# 00_POWER.net
KiCad netlist of a schematic drawn in Altium Designer
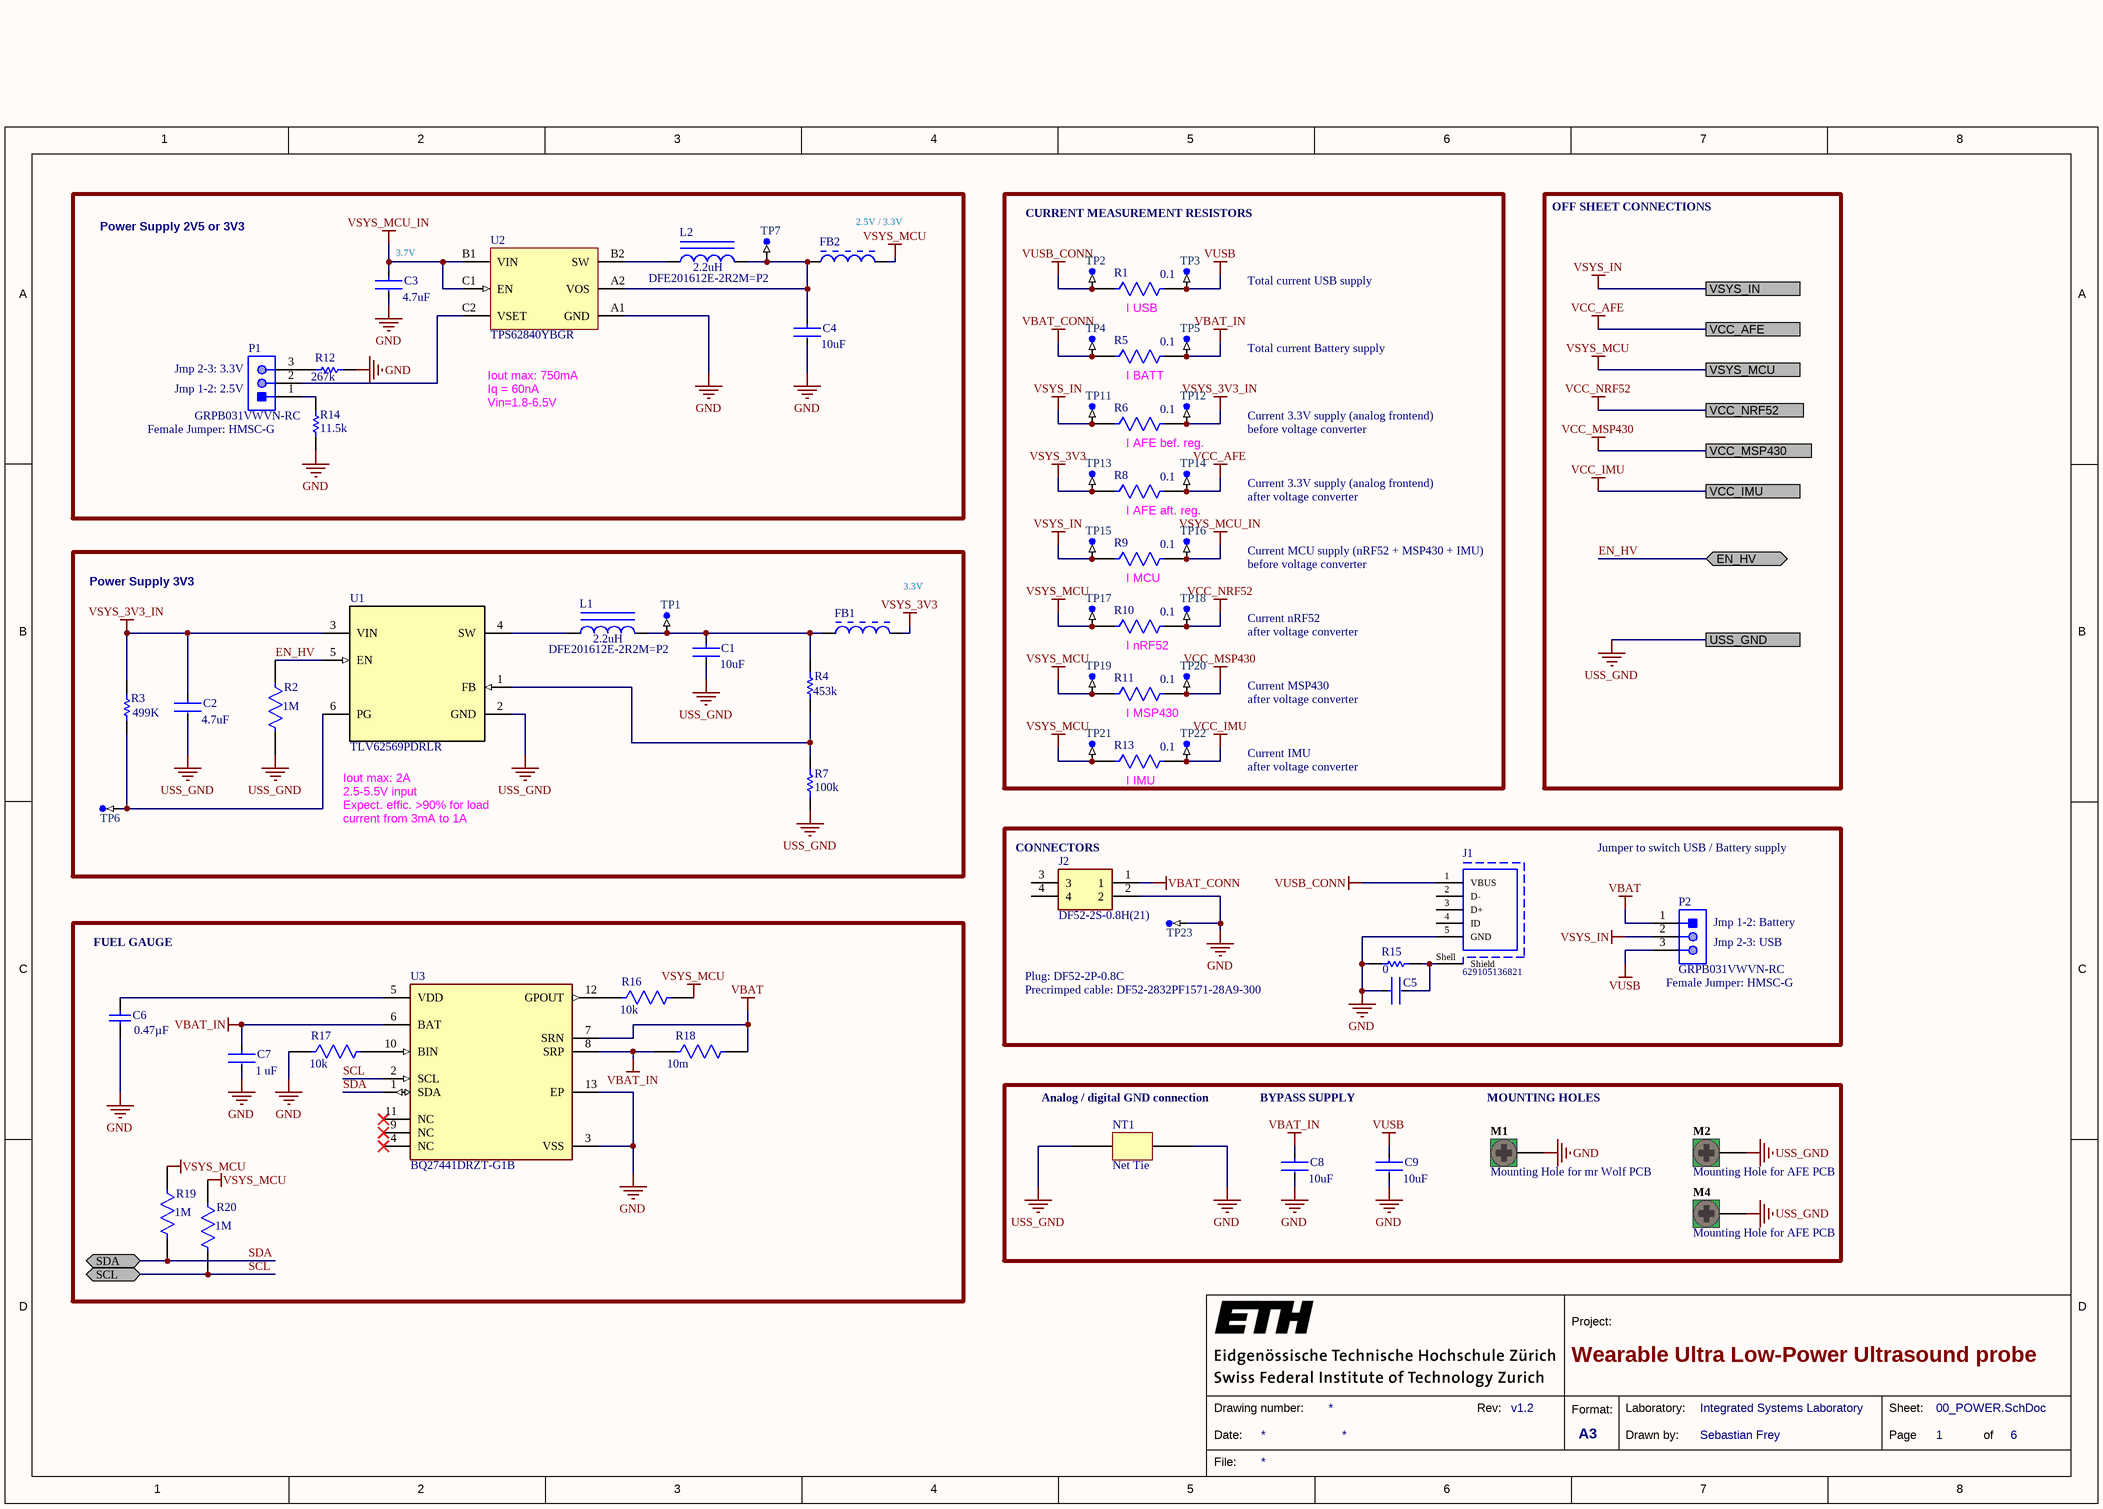
[diagram p0: 00_POWER.SchDoc]

(export (version "E")
  (design (tool "Eeschema 10.0.6"))
  (components
    (comp (ref "C1")
      (value "10uF")
      (footprint "FP-C1608-080-MFG")
      (description "CAP CER 10UF 10V X5R 0603")
      (fields
        (field (name "MANUFACTURER PART NUMBER") "C1608X5R1A106K080AC")
        (field (name "OCTOPART") "https://octopart.com/c1608x5r1a106k080ac-tdk-26013468")
      )
      (libsource (lib "Altium Content Vault") (part "11868f565c42a9108669ba33697ecf6"))
    )
    (comp (ref "C2")
      (value "EMK107ABJ475KA-T")
      (footprint "FP-0603-L_1_6_0_15-W_0_8-IPC_A")
      (description "None")
      (fields (field (name "CAPACITANCE") "4.7uF") (field (name "TOLERANCE") "10%"))
      (libsource (lib "Altium Content Vault") (part "11868f565c42a9108669ba33697ecf6"))
    )
    (comp (ref "C3")
      (value "EMK107ABJ475KA-T")
      (footprint "FP-0603-L_1_6_0_15-W_0_8-IPC_A")
      (description "None")
      (fields (field (name "CAPACITANCE") "4.7uF") (field (name "TOLERANCE") "10%"))
      (libsource (lib "Altium Content Vault") (part "11868f565c42a9108669ba33697ecf6"))
    )
    (comp (ref "C4")
      (value "10uF")
      (footprint "FP-C1608-080-MFG")
      (description "CAP CER 10UF 10V X5R 0603")
      (fields
        (field (name "MANUFACTURER PART NUMBER") "C1608X5R1A106K080AC")
        (field (name "OCTOPART") "https://octopart.com/c1608x5r1a106k080ac-tdk-26013468")
      )
      (libsource (lib "Altium Content Vault") (part "11868f565c42a9108669ba33697ecf6"))
    )
    (comp (ref "C5")
      (value "CC0402KRX7R7BB104")
      (footprint "FP-CC0402-MFG")
      (description "CAP CER 0.1UF 16V X7R 0402")
      (fields (field (name "MANUFACTURER") "YAGEO") (field (name "TOLERANCE") "0.1"))
      (libsource (lib "Altium Content Vault") (part "11868f565c42a9108669ba33697ecf6"))
    )
    (comp (ref "C6")
      (value "C1005X5R1E474K050BB")
      (footprint "CAPC1050X55X10LL05")
      (description "Chip Capacitor, 0.47 uF, +/- 10%, 25 V, -55 to 85 degC, 0402 (1005 Metric), RoHS, Tape and Reel")
      (fields
        (field (name "CAPACITANCE") "0.47µF")
        (field (name "TOLERANCE") "±10%")
        (field (name "PCN PART NUMBER") "MLCCPartNumberChange30/Nov/2012")
      )
      (libsource (lib "Altium Content Vault") (part "CAP-NP-2"))
    )
    (comp (ref "C7")
      (value "CC0402KRX5R5BB105")
      (footprint "FP-CC0402-MFG")
      (description "CAP CER 1UF 6.3V X5R 0402")
      (fields
        (field (name "CAPACITANCE") "1 uF")
        (field (name "MANUFACTURER") "YAGEO")
        (field (name "OCTOPART") "https://octopart.com/cc0402krx5r5bb105-yageo-42244618")
      )
      (libsource (lib "Altium Content Vault") (part "11868f565c42a9108669ba33697ecf6"))
    )
    (comp (ref "C8")
      (value "10uF")
      (footprint "FP-C1608-080-MFG")
      (description "CAP CER 10UF 10V X5R 0603")
      (fields
        (field (name "MANUFACTURER PART NUMBER") "C1608X5R1A106K080AC")
        (field (name "OCTOPART") "https://octopart.com/c1608x5r1a106k080ac-tdk-26013468")
      )
      (libsource (lib "Altium Content Vault") (part "11868f565c42a9108669ba33697ecf6"))
    )
    (comp (ref "C9")
      (value "10uF")
      (footprint "FP-C1608-080-MFG")
      (description "CAP CER 10UF 10V X5R 0603")
      (fields
        (field (name "MANUFACTURER PART NUMBER") "C1608X5R1A106K080AC")
        (field (name "OCTOPART") "https://octopart.com/c1608x5r1a106k080ac-tdk-26013468")
      )
      (libsource (lib "Altium Content Vault") (part "11868f565c42a9108669ba33697ecf6"))
    )
    (comp (ref "FB1")
      (value "BLM03AX800SN1D")
      (footprint "MURA-BLM03-CHIP-2_V")
      (fields (field (name "MANUFACTURER") "Murata") (field (name "TOLERANCE") "25%"))
      (libsource (lib "Altium Content Vault") (part "MURA-FB-2"))
    )
    (comp (ref "FB2")
      (value "BLM03AX800SN1D")
      (footprint "MURA-BLM03-CHIP-2_V")
      (fields (field (name "MANUFACTURER") "Murata") (field (name "TOLERANCE") "25%"))
      (libsource (lib "Altium Content Vault") (part "MURA-FB-2"))
    )
    (comp (ref "J1")
      (value "629105136821")
      (footprint "629105136821")
      (description "Micro USB 2.0 Type B Receptacle WR-COM, Horizontal, SMT, with Pads and Pegs")
      (fields (field (name "MANUFACTURER") "Wurth Elektronik") (field (name "PUBLISHER") "WurthElektronik"))
      (libsource (lib "Altium Content Vault") (part "WE-USB-5-1SHLD"))
    )
    (comp (ref "J2")
      (value "DF52-2S-0.8H(21)")
      (footprint "SamacSys:DF522S08H21")
      (description "Connector")
      (fields (field (name "MOUSER PART NUMBER") "798-DF52-2S-0.8H21"))
      (libsource (lib "*") (part "DF52-2S-0.8H_21_"))
    )
    (comp (ref "L1")
      (value "DFE201612E-2R2M=P2")
      (footprint "INDC2016X10L")
      (description "2.2µH Shielded Wirewound Inductor 1.8A 116mOhm Max 0806 (2016 Metric)")
      (fields
        (field (name "ALTIUM_VALUE") "2.2uH")
        (field (name "TOLERANCE") "±20%")
        (field (name "MANUFACTURER") "Murata Electronics")
      )
      (libsource (lib "ETHZ Vault") (part "Iron Core Inductor"))
    )
    (comp (ref "L2")
      (value "DFE201612E-2R2M=P2")
      (footprint "INDC2016X10L")
      (description "2.2µH Shielded Wirewound Inductor 1.8A 116mOhm Max 0806 (2016 Metric)")
      (fields
        (field (name "ALTIUM_VALUE") "2.2uH")
        (field (name "TOLERANCE") "±20%")
        (field (name "MANUFACTURER") "Murata Electronics")
      )
      (libsource (lib "ETHZ Vault") (part "Iron Core Inductor"))
    )
    (comp (ref "M1")
      (value "Mounting Hole for mr Wolf PCB")
      (footprint "Hole M2")
      (description "M2 Hole, 2.4mm drill, 5mm landing pads, 3mm pad in middle layers, no overlay")
      (libsource (lib "ETHZ Vault") (part "Hole"))
    )
    (comp (ref "M2")
      (value "Mounting Hole for AFE PCB")
      (footprint "Hole M2")
      (description "M2 Hole, 2.4mm drill, 5mm landing pads, 3mm pad in middle layers, no overlay")
      (libsource (lib "ETHZ Vault") (part "Hole"))
    )
    (comp (ref "M4")
      (value "Mounting Hole for AFE PCB")
      (footprint "Hole M2")
      (description "M2 Hole, 2.4mm drill, 5mm landing pads, 3mm pad in middle layers, no overlay")
      (libsource (lib "ETHZ Vault") (part "Hole"))
    )
    (comp (ref "NT1")
      (value "Net Tie")
      (footprint "PcbLib1:Net_Tie_Top_Bottom")
      (libsource (lib "Schlib1") (part "Net_Tie"))
    )
    (comp (ref "P1")
      (value "GRPB031VWVN-RC")
      (footprint "SLIN-GRPB031VWVN-RC_V")
      (fields (field (name "MANUFACTURER") "Sullins"))
      (libsource (lib "") (part "CN-1P-M-R3_1"))
    )
    (comp (ref "P2")
      (value "GRPB031VWVN-RC")
      (footprint "SLIN-GRPB031VWVN-RC_V")
      (fields (field (name "MANUFACTURER") "Sullins"))
      (libsource (lib "Altium Content Vault") (part "CN-1P-M-R3"))
    )
    (comp (ref "R1")
      (value "ERJ-2BWFR100X")
      (footprint "FP-CSR0402-MFG")
      (description "RES 0.1 OHM 1% 1/4W 0402")
      (fields (field (name "TOLERANCE") "1%") (field (name "RESISTANCE") "0.1"))
      (libsource (lib "Altium Content Vault") (part "1029c3af85768c4190bb7ad29bc67b5"))
    )
    (comp (ref "R2")
      (value "CR0402-JW-105GLF")
      (footprint "FP-CR0402-MFG")
      (description "Thick Film Chip Resistors 0402 1MΩ 0.0625W 5% 200ppm/°C")
      (fields (field (name "TOLERANCE") "5%") (field (name "RESISTANCE") "1M"))
      (libsource (lib "Altium Content Vault") (part "1029c3af85768c4190bb7ad29bc67b5"))
    )
    (comp (ref "R3")
      (value "499K")
      (footprint "RESC0402(1005)_N")
      (description "499K 0.063W 1% 0402 (1005 Metric)  SMD")
      (fields (field (name "TOLERANCE") "1 %") (field (name "POWER") "0.063 W"))
      (libsource (lib "Altium Content Vault") (part "RES"))
    )
    (comp (ref "R4")
      (value "RC0402FR-07453KL")
      (footprint "RESC1005X40X25NL05T10")
      (fields (field (name "MANUFACTURER") "Yageo") (field (name "RESISTANCE") "453k"))
      (libsource (lib "Altium Content Vault") (part "RES"))
    )
    (comp (ref "R5")
      (value "ERJ-2BWFR100X")
      (footprint "FP-CSR0402-MFG")
      (description "RES 0.1 OHM 1% 1/4W 0402")
      (fields (field (name "TOLERANCE") "1%") (field (name "RESISTANCE") "0.1"))
      (libsource (lib "Altium Content Vault") (part "1029c3af85768c4190bb7ad29bc67b5"))
    )
    (comp (ref "R6")
      (value "ERJ-2BWFR100X")
      (footprint "FP-CSR0402-MFG")
      (description "RES 0.1 OHM 1% 1/4W 0402")
      (fields (field (name "TOLERANCE") "1%") (field (name "RESISTANCE") "0.1"))
      (libsource (lib "Altium Content Vault") (part "1029c3af85768c4190bb7ad29bc67b5"))
    )
    (comp (ref "R7")
      (value "RMCF0402FT100K")
      (footprint "RESC1005X40X25LL10T15")
      (description "Chip Resistor, 100 KOhm, +/- 1%, 63 mW, -55 to 155 degC, 0402 (1005 Metric), RoHS, Tape and Reel")
      (fields
        (field (name "RESISTANCE (OHMS)") "100k")
        (field (name "MANUFACTURER") "Stackpole-Electronics-Inc.")
        (field (name "TOLERANCE") "±1%")
      )
      (libsource (lib "Altium Content Vault") (part "RES-2"))
    )
    (comp (ref "R8")
      (value "ERJ-2BWFR100X")
      (footprint "FP-CSR0402-MFG")
      (description "RES 0.1 OHM 1% 1/4W 0402")
      (fields (field (name "TOLERANCE") "1%") (field (name "RESISTANCE") "0.1"))
      (libsource (lib "Altium Content Vault") (part "1029c3af85768c4190bb7ad29bc67b5"))
    )
    (comp (ref "R9")
      (value "ERJ-2BWFR100X")
      (footprint "FP-CSR0402-MFG")
      (description "RES 0.1 OHM 1% 1/4W 0402")
      (fields (field (name "TOLERANCE") "1%") (field (name "RESISTANCE") "0.1"))
      (libsource (lib "Altium Content Vault") (part "1029c3af85768c4190bb7ad29bc67b5"))
    )
    (comp (ref "R10")
      (value "ERJ-2BWFR100X")
      (footprint "FP-CSR0402-MFG")
      (description "RES 0.1 OHM 1% 1/4W 0402")
      (fields (field (name "TOLERANCE") "1%") (field (name "RESISTANCE") "0.1"))
      (libsource (lib "Altium Content Vault") (part "1029c3af85768c4190bb7ad29bc67b5"))
    )
    (comp (ref "R11")
      (value "ERJ-2BWFR100X")
      (footprint "FP-CSR0402-MFG")
      (description "RES 0.1 OHM 1% 1/4W 0402")
      (fields (field (name "TOLERANCE") "1%") (field (name "RESISTANCE") "0.1"))
      (libsource (lib "Altium Content Vault") (part "1029c3af85768c4190bb7ad29bc67b5"))
    )
    (comp (ref "R12")
      (value "CRCW0402267KFKED")
      (footprint "RESC1005X40X25LL05T05")
      (fields (field (name "MANUFACTURER") "Vishay Dale") (field (name "RESISTANCE") "267k"))
      (libsource (lib "Altium Content Vault") (part "RES"))
    )
    (comp (ref "R13")
      (value "ERJ-2BWFR100X")
      (footprint "FP-CSR0402-MFG")
      (description "RES 0.1 OHM 1% 1/4W 0402")
      (fields (field (name "TOLERANCE") "1%") (field (name "RESISTANCE") "0.1"))
      (libsource (lib "Altium Content Vault") (part "1029c3af85768c4190bb7ad29bc67b5"))
    )
    (comp (ref "R14")
      (value "RC0402FR-0711K5L")
      (footprint "RESC1005X40X25ML05T10")
      (fields (field (name "MANUFACTURER") "Yageo / Phycomp") (field (name "RESISTANCE") "11.5k"))
      (libsource (lib "Altium Content Vault") (part "RES"))
    )
    (comp (ref "R15")
      (value "RC0402JR-070RL")
      (footprint "RESC1005X40X25NL05T10")
      (fields (field (name "MANUFACTURER") "Yageo / Phycomp") (field (name "RESISTANCE") "0"))
      (libsource (lib "Altium Content Vault") (part "RES"))
    )
    (comp (ref "R16")
      (value "10k")
      (footprint "FP-TNPW0402-e3-MFG")
      (description "RES 10K OHM 0.1% 1/10W 0402")
      (fields (field (name "MANUFACTURER PART NUMBER") "TNPW040210K0BEED") (field (name "TOLERANCE") "0.1%"))
      (libsource (lib "Altium Content Vault") (part "1029c3af85768c4190bb7ad29bc67b5"))
    )
    (comp (ref "R17")
      (value "10k")
      (footprint "FP-TNPW0402-e3-MFG")
      (description "RES 10K OHM 0.1% 1/10W 0402")
      (fields (field (name "MANUFACTURER PART NUMBER") "TNPW040210K0BEED") (field (name "TOLERANCE") "0.1%"))
      (libsource (lib "Altium Content Vault") (part "1029c3af85768c4190bb7ad29bc67b5"))
    )
    (comp (ref "R18")
      (value "CSRF0402FT10L0")
      (footprint "FP-CSRF0402-high-IPC_A")
      (description "RES 0.01 OHM 1% 1/8W 0402")
      (fields (field (name "RESISTANCE") "10m") (field (name "TOLERANCE") "1%"))
      (libsource (lib "Altium Content Vault") (part "1029c3af85768c4190bb7ad29bc67b5"))
    )
    (comp (ref "R19")
      (value "CR0402-JW-105GLF")
      (footprint "FP-CR0402-MFG")
      (description "Thick Film Chip Resistors 0402 1MΩ 0.0625W 5% 200ppm/°C")
      (fields (field (name "TOLERANCE") "5%") (field (name "RESISTANCE") "1M"))
      (libsource (lib "Altium Content Vault") (part "1029c3af85768c4190bb7ad29bc67b5"))
    )
    (comp (ref "R20")
      (value "CR0402-JW-105GLF")
      (footprint "FP-CR0402-MFG")
      (description "Thick Film Chip Resistors 0402 1MΩ 0.0625W 5% 200ppm/°C")
      (fields (field (name "TOLERANCE") "5%") (field (name "RESISTANCE") "1M"))
      (libsource (lib "Altium Content Vault") (part "1029c3af85768c4190bb7ad29bc67b5"))
    )
    (comp (ref "TP1")
      (value "TP-SM-C-100")
      (footprint "TP-SM-C-100")
      (description "Test Point, Surface Mount, Circular, Pad Diameter 1 mm")
      (libsource (lib "Altium Content Vault") (part "TP-SM"))
    )
    (comp (ref "TP2")
      (value "TP-SM-C-100")
      (footprint "TP-SM-C-100")
      (description "Test Point, Surface Mount, Circular, Pad Diameter 1 mm")
      (libsource (lib "Altium Content Vault") (part "TP-SM"))
    )
    (comp (ref "TP3")
      (value "TP-SM-C-100")
      (footprint "TP-SM-C-100")
      (description "Test Point, Surface Mount, Circular, Pad Diameter 1 mm")
      (libsource (lib "Altium Content Vault") (part "TP-SM"))
    )
    (comp (ref "TP4")
      (value "TP-SM-C-100")
      (footprint "TP-SM-C-100")
      (description "Test Point, Surface Mount, Circular, Pad Diameter 1 mm")
      (libsource (lib "Altium Content Vault") (part "TP-SM"))
    )
    (comp (ref "TP5")
      (value "TP-SM-C-100")
      (footprint "TP-SM-C-100")
      (description "Test Point, Surface Mount, Circular, Pad Diameter 1 mm")
      (libsource (lib "Altium Content Vault") (part "TP-SM"))
    )
    (comp (ref "TP6")
      (value "TP-SM-C-100")
      (footprint "TP-SM-C-100")
      (description "Test Point, Surface Mount, Circular, Pad Diameter 1 mm")
      (libsource (lib "Altium Content Vault") (part "TP-SM"))
    )
    (comp (ref "TP7")
      (value "TP-SM-C-100")
      (footprint "TP-SM-C-100")
      (description "Test Point, Surface Mount, Circular, Pad Diameter 1 mm")
      (libsource (lib "Altium Content Vault") (part "TP-SM"))
    )
    (comp (ref "TP11")
      (value "TP-SM-C-100")
      (footprint "TP-SM-C-100")
      (description "Test Point, Surface Mount, Circular, Pad Diameter 1 mm")
      (libsource (lib "Altium Content Vault") (part "TP-SM"))
    )
    (comp (ref "TP12")
      (value "TP-SM-C-100")
      (footprint "TP-SM-C-100")
      (description "Test Point, Surface Mount, Circular, Pad Diameter 1 mm")
      (libsource (lib "Altium Content Vault") (part "TP-SM"))
    )
    (comp (ref "TP13")
      (value "TP-SM-C-100")
      (footprint "TP-SM-C-100")
      (description "Test Point, Surface Mount, Circular, Pad Diameter 1 mm")
      (libsource (lib "Altium Content Vault") (part "TP-SM"))
    )
    (comp (ref "TP14")
      (value "TP-SM-C-100")
      (footprint "TP-SM-C-100")
      (description "Test Point, Surface Mount, Circular, Pad Diameter 1 mm")
      (libsource (lib "Altium Content Vault") (part "TP-SM"))
    )
    (comp (ref "TP15")
      (value "TP-SM-C-100")
      (footprint "TP-SM-C-100")
      (description "Test Point, Surface Mount, Circular, Pad Diameter 1 mm")
      (libsource (lib "Altium Content Vault") (part "TP-SM"))
    )
    (comp (ref "TP16")
      (value "TP-SM-C-100")
      (footprint "TP-SM-C-100")
      (description "Test Point, Surface Mount, Circular, Pad Diameter 1 mm")
      (libsource (lib "Altium Content Vault") (part "TP-SM"))
    )
    (comp (ref "TP17")
      (value "TP-SM-C-100")
      (footprint "TP-SM-C-100")
      (description "Test Point, Surface Mount, Circular, Pad Diameter 1 mm")
      (libsource (lib "Altium Content Vault") (part "TP-SM"))
    )
    (comp (ref "TP18")
      (value "TP-SM-C-100")
      (footprint "TP-SM-C-100")
      (description "Test Point, Surface Mount, Circular, Pad Diameter 1 mm")
      (libsource (lib "Altium Content Vault") (part "TP-SM"))
    )
    (comp (ref "TP19")
      (value "TP-SM-C-100")
      (footprint "TP-SM-C-100")
      (description "Test Point, Surface Mount, Circular, Pad Diameter 1 mm")
      (libsource (lib "Altium Content Vault") (part "TP-SM"))
    )
    (comp (ref "TP20")
      (value "TP-SM-C-100")
      (footprint "TP-SM-C-100")
      (description "Test Point, Surface Mount, Circular, Pad Diameter 1 mm")
      (libsource (lib "Altium Content Vault") (part "TP-SM"))
    )
    (comp (ref "TP21")
      (value "TP-SM-C-100")
      (footprint "TP-SM-C-100")
      (description "Test Point, Surface Mount, Circular, Pad Diameter 1 mm")
      (libsource (lib "Altium Content Vault") (part "TP-SM"))
    )
    (comp (ref "TP22")
      (value "TP-SM-C-100")
      (footprint "TP-SM-C-100")
      (description "Test Point, Surface Mount, Circular, Pad Diameter 1 mm")
      (libsource (lib "Altium Content Vault") (part "TP-SM"))
    )
    (comp (ref "TP23")
      (value "TP-SM-C-100")
      (footprint "TP-SM-C-100")
      (description "Test Point, Surface Mount, Circular, Pad Diameter 1 mm")
      (libsource (lib "Altium Content Vault") (part "TP-SM"))
    )
    (comp (ref "U1")
      (value "TLV62569PDRLR")
      (footprint "PcbLib1:TLV62569PDRLR")
      (fields (field (name "MANUFACTURER") "Texas Instruments"))
      (libsource (lib "Schlib1") (part "TLV62569PDRLR"))
    )
    (comp (ref "U2")
      (value "TPS62840YBGR")
      (footprint "BGA6C40P2X3_97X147X50")
      (fields (field (name "MANUFACTURER") "Texas Instruments"))
      (libsource (lib "ETHZ Vault") (part "TPS62840YBGR"))
    )
    (comp (ref "U3")
      (value "BQ27441DRZT-G1B")
      (footprint "PcbLib1:DRZ0012A_MFG")
      (description "System-side Impedance Track™ battery fuel (gas) gauge 12-SON -40 to 85")
      (fields (field (name "MANUFACTURER") "Texas Instruments"))
      (libsource (lib "Schlib1") (part "BQ27441DRZT-G1B"))
    )
  )
  (nets
    (net (code "1") (name "/EN_HV") (class "Default")
      (node (ref "R2") (pin "1") (pinfunction "1_1") (pintype "passive"))
      (node (ref "U1") (pin "5") (pinfunction "EN_5") (pintype "input"))
    )
    (net (code "2") (name "/SCL") (class "Default")
      (node (ref "R20") (pin "2") (pinfunction "2_2") (pintype "passive"))
      (node (ref "U3") (pin "2") (pinfunction "SCL_2") (pintype "input"))
    )
    (net (code "3") (name "/SDA") (class "Default")
      (node (ref "R19") (pin "2") (pinfunction "2_2") (pintype "passive"))
      (node (ref "U3") (pin "1") (pinfunction "SDA_1") (pintype "bidirectional"))
    )
    (net (code "4") (name "GND") (class "Default")
      (node (ref "C3") (pin "2") (pinfunction "2_2") (pintype "passive"))
      (node (ref "C4") (pin "2") (pinfunction "2_2") (pintype "passive"))
      (node (ref "C5") (pin "1") (pinfunction "1_1") (pintype "passive"))
      (node (ref "C6") (pin "1") (pinfunction "1_1") (pintype "passive"))
      (node (ref "C7") (pin "2") (pinfunction "2_2") (pintype "passive"))
      (node (ref "C8") (pin "2") (pinfunction "2_2") (pintype "passive"))
      (node (ref "C9") (pin "2") (pinfunction "2_2") (pintype "passive"))
      (node (ref "J1") (pin "5") (pinfunction "GND_5") (pintype "passive"))
      (node (ref "J2") (pin "2") (pinfunction "2_2") (pintype "passive"))
      (node (ref "M1") (pin "1") (pinfunction "1_1") (pintype "passive"))
      (node (ref "NT1") (pin "2") (pinfunction "2_2") (pintype "passive"))
      (node (ref "R12") (pin "1") (pinfunction "1_1") (pintype "passive"))
      (node (ref "R14") (pin "1") (pinfunction "1_1") (pintype "passive"))
      (node (ref "R15") (pin "2") (pinfunction "2_2") (pintype "passive"))
      (node (ref "R17") (pin "1") (pinfunction "1_1") (pintype "passive"))
      (node (ref "TP23") (pin "1") (pinfunction "1_1") (pintype "input"))
      (node (ref "U2") (pin "A1") (pinfunction "GND_A1") (pintype "power_in"))
      (node (ref "U3") (pin "13") (pinfunction "EP_13") (pintype "passive"))
      (node (ref "U3") (pin "3") (pinfunction "VSS_3") (pintype "power_in"))
    )
    (net (code "5") (name "Net-(C1-Pad1)") (class "Default")
      (node (ref "C1") (pin "1") (pinfunction "1_1") (pintype "passive"))
      (node (ref "FB1") (pin "1") (pinfunction "1_1") (pintype "passive"))
      (node (ref "L1") (pin "2") (pinfunction "2_2") (pintype "passive"))
      (node (ref "R4") (pin "2") (pinfunction "2_2") (pintype "passive"))
      (node (ref "TP1") (pin "1") (pinfunction "1_1") (pintype "input"))
    )
    (net (code "6") (name "Net-(J1-Shield)") (class "Default")
      (node (ref "C5") (pin "2") (pinfunction "2_2") (pintype "passive"))
      (node (ref "J1") (pin "Shell") (pinfunction "Shield_Shell") (pintype "passive"))
      (node (ref "R15") (pin "1") (pinfunction "1_1") (pintype "passive"))
    )
    (net (code "7") (name "Net-(P1-Pad1)") (class "Default")
      (node (ref "P1") (pin "1") (pinfunction "1_1") (pintype "passive"))
      (node (ref "R14") (pin "2") (pinfunction "2_2") (pintype "passive"))
    )
    (net (code "8") (name "Net-(P1-Pad3)") (class "Default")
      (node (ref "P1") (pin "3") (pinfunction "3_3") (pintype "passive"))
      (node (ref "R12") (pin "2") (pinfunction "2_2") (pintype "passive"))
    )
    (net (code "9") (name "Net-(U1-FB)") (class "Default")
      (node (ref "R4") (pin "1") (pinfunction "1_1") (pintype "passive"))
      (node (ref "R7") (pin "2") (pinfunction "2_2") (pintype "passive"))
      (node (ref "U1") (pin "1") (pinfunction "FB_1") (pintype "input"))
    )
    (net (code "10") (name "Net-(U1-PG)") (class "Default")
      (node (ref "R3") (pin "1") (pinfunction "1_1") (pintype "passive"))
      (node (ref "TP6") (pin "1") (pinfunction "1_1") (pintype "input"))
      (node (ref "U1") (pin "6") (pinfunction "PG_6") (pintype "open_collector"))
    )
    (net (code "11") (name "Net-(U1-SW)") (class "Default")
      (node (ref "L1") (pin "1") (pinfunction "1_1") (pintype "passive"))
      (node (ref "U1") (pin "4") (pinfunction "SW_4") (pintype "power_in"))
    )
    (net (code "12") (name "Net-(U2-SW)") (class "Default")
      (node (ref "L2") (pin "1") (pinfunction "1_1") (pintype "passive"))
      (node (ref "U2") (pin "B2") (pinfunction "SW_B2") (pintype "power_in"))
    )
    (net (code "13") (name "Net-(U2-VOS)") (class "Default")
      (node (ref "C4") (pin "1") (pinfunction "1_1") (pintype "passive"))
      (node (ref "FB2") (pin "1") (pinfunction "1_1") (pintype "passive"))
      (node (ref "L2") (pin "2") (pinfunction "2_2") (pintype "passive"))
      (node (ref "TP7") (pin "1") (pinfunction "1_1") (pintype "input"))
      (node (ref "U2") (pin "A2") (pinfunction "VOS_A2") (pintype "passive"))
    )
    (net (code "14") (name "Net-(U2-VSET)") (class "Default")
      (node (ref "P1") (pin "2") (pinfunction "2_2") (pintype "passive"))
      (node (ref "U2") (pin "C2") (pinfunction "VSET_C2") (pintype "passive"))
    )
    (net (code "15") (name "Net-(U3-BIN)") (class "Default")
      (node (ref "R17") (pin "2") (pinfunction "2_2") (pintype "passive"))
      (node (ref "U3") (pin "10") (pinfunction "BIN_10") (pintype "input"))
    )
    (net (code "16") (name "Net-(U3-GPOUT)") (class "Default")
      (node (ref "R16") (pin "1") (pinfunction "1_1") (pintype "passive"))
      (node (ref "U3") (pin "12") (pinfunction "GPOUT_12") (pintype "output"))
    )
    (net (code "17") (name "Net-(U3-VDD)") (class "Default")
      (node (ref "C6") (pin "2") (pinfunction "2_2") (pintype "passive"))
      (node (ref "U3") (pin "5") (pinfunction "VDD_5") (pintype "power_in"))
    )
    (net (code "18") (name "USS_GND") (class "Default")
      (node (ref "C1") (pin "2") (pinfunction "2_2") (pintype "passive"))
      (node (ref "C2") (pin "2") (pinfunction "2_2") (pintype "passive"))
      (node (ref "M2") (pin "1") (pinfunction "1_1") (pintype "passive"))
      (node (ref "M4") (pin "1") (pinfunction "1_1") (pintype "passive"))
      (node (ref "NT1") (pin "1") (pinfunction "1_1") (pintype "passive"))
      (node (ref "R2") (pin "2") (pinfunction "2_2") (pintype "passive"))
      (node (ref "R7") (pin "1") (pinfunction "1_1") (pintype "passive"))
      (node (ref "U1") (pin "2") (pinfunction "GND_2") (pintype "power_in"))
    )
    (net (code "19") (name "VBAT") (class "Default")
      (node (ref "P2") (pin "1") (pinfunction "1_1") (pintype "passive"))
      (node (ref "R18") (pin "2") (pinfunction "2_2") (pintype "passive"))
      (node (ref "U3") (pin "7") (pinfunction "SRN_7") (pintype "passive"))
    )
    (net (code "20") (name "VBAT_CONN") (class "Default")
      (node (ref "J2") (pin "1") (pinfunction "1_1") (pintype "passive"))
      (node (ref "R5") (pin "1") (pinfunction "1_1") (pintype "passive"))
      (node (ref "TP4") (pin "1") (pinfunction "1_1") (pintype "input"))
    )
    (net (code "21") (name "VBAT_IN") (class "Default")
      (node (ref "C7") (pin "1") (pinfunction "1_1") (pintype "passive"))
      (node (ref "C8") (pin "1") (pinfunction "1_1") (pintype "passive"))
      (node (ref "R18") (pin "1") (pinfunction "1_1") (pintype "passive"))
      (node (ref "R5") (pin "2") (pinfunction "2_2") (pintype "passive"))
      (node (ref "TP5") (pin "1") (pinfunction "1_1") (pintype "input"))
      (node (ref "U3") (pin "6") (pinfunction "BAT_6") (pintype "passive"))
      (node (ref "U3") (pin "8") (pinfunction "SRP_8") (pintype "passive"))
    )
    (net (code "22") (name "VCC_AFE") (class "Default")
      (node (ref "R8") (pin "2") (pinfunction "2_2") (pintype "passive"))
      (node (ref "TP14") (pin "1") (pinfunction "1_1") (pintype "input"))
    )
    (net (code "23") (name "VCC_IMU") (class "Default")
      (node (ref "R13") (pin "2") (pinfunction "2_2") (pintype "passive"))
      (node (ref "TP22") (pin "1") (pinfunction "1_1") (pintype "input"))
    )
    (net (code "24") (name "VCC_MSP430") (class "Default")
      (node (ref "R11") (pin "2") (pinfunction "2_2") (pintype "passive"))
      (node (ref "TP20") (pin "1") (pinfunction "1_1") (pintype "input"))
    )
    (net (code "25") (name "VCC_NRF52") (class "Default")
      (node (ref "R10") (pin "2") (pinfunction "2_2") (pintype "passive"))
      (node (ref "TP18") (pin "1") (pinfunction "1_1") (pintype "input"))
    )
    (net (code "26") (name "VSYS_3V3") (class "Default")
      (node (ref "FB1") (pin "2") (pinfunction "2_2") (pintype "passive"))
      (node (ref "R8") (pin "1") (pinfunction "1_1") (pintype "passive"))
      (node (ref "TP13") (pin "1") (pinfunction "1_1") (pintype "input"))
    )
    (net (code "27") (name "VSYS_3V3_IN") (class "Default")
      (node (ref "C2") (pin "1") (pinfunction "1_1") (pintype "passive"))
      (node (ref "R3") (pin "2") (pinfunction "2_2") (pintype "passive"))
      (node (ref "R6") (pin "2") (pinfunction "2_2") (pintype "passive"))
      (node (ref "TP12") (pin "1") (pinfunction "1_1") (pintype "input"))
      (node (ref "U1") (pin "3") (pinfunction "VIN_3") (pintype "power_in"))
    )
    (net (code "28") (name "VSYS_IN") (class "Default")
      (node (ref "P2") (pin "2") (pinfunction "2_2") (pintype "passive"))
      (node (ref "R6") (pin "1") (pinfunction "1_1") (pintype "passive"))
      (node (ref "R9") (pin "1") (pinfunction "1_1") (pintype "passive"))
      (node (ref "TP11") (pin "1") (pinfunction "1_1") (pintype "input"))
      (node (ref "TP15") (pin "1") (pinfunction "1_1") (pintype "input"))
    )
    (net (code "29") (name "VSYS_MCU") (class "Default")
      (node (ref "FB2") (pin "2") (pinfunction "2_2") (pintype "passive"))
      (node (ref "R10") (pin "1") (pinfunction "1_1") (pintype "passive"))
      (node (ref "R11") (pin "1") (pinfunction "1_1") (pintype "passive"))
      (node (ref "R13") (pin "1") (pinfunction "1_1") (pintype "passive"))
      (node (ref "R16") (pin "2") (pinfunction "2_2") (pintype "passive"))
      (node (ref "R19") (pin "1") (pinfunction "1_1") (pintype "passive"))
      (node (ref "R20") (pin "1") (pinfunction "1_1") (pintype "passive"))
      (node (ref "TP17") (pin "1") (pinfunction "1_1") (pintype "input"))
      (node (ref "TP19") (pin "1") (pinfunction "1_1") (pintype "input"))
      (node (ref "TP21") (pin "1") (pinfunction "1_1") (pintype "input"))
    )
    (net (code "30") (name "VSYS_MCU_IN") (class "Default")
      (node (ref "C3") (pin "1") (pinfunction "1_1") (pintype "passive"))
      (node (ref "R9") (pin "2") (pinfunction "2_2") (pintype "passive"))
      (node (ref "TP16") (pin "1") (pinfunction "1_1") (pintype "input"))
      (node (ref "U2") (pin "B1") (pinfunction "VIN_B1") (pintype "power_in"))
      (node (ref "U2") (pin "C1") (pinfunction "EN_C1") (pintype "input"))
    )
    (net (code "31") (name "VUSB") (class "Default")
      (node (ref "C9") (pin "1") (pinfunction "1_1") (pintype "passive"))
      (node (ref "P2") (pin "3") (pinfunction "3_3") (pintype "passive"))
      (node (ref "R1") (pin "2") (pinfunction "2_2") (pintype "passive"))
      (node (ref "TP3") (pin "1") (pinfunction "1_1") (pintype "input"))
    )
    (net (code "32") (name "VUSB_CONN") (class "Default")
      (node (ref "J1") (pin "1") (pinfunction "VBUS_1") (pintype "passive"))
      (node (ref "R1") (pin "1") (pinfunction "1_1") (pintype "passive"))
      (node (ref "TP2") (pin "1") (pinfunction "1_1") (pintype "input"))
    )
    (net (code "33") (name "unconnected-(J1-D+-Pad3)") (class "Default")
      (node (ref "J1") (pin "3") (pinfunction "D+_3") (pintype "passive"))
    )
    (net (code "34") (name "unconnected-(J1-D--Pad2)") (class "Default")
      (node (ref "J1") (pin "2") (pinfunction "D-_2") (pintype "passive"))
    )
    (net (code "35") (name "unconnected-(J1-ID-Pad4)") (class "Default")
      (node (ref "J1") (pin "4") (pinfunction "ID_4") (pintype "passive"))
    )
    (net (code "36") (name "unconnected-(J2-Pad3)") (class "Default")
      (node (ref "J2") (pin "3") (pinfunction "3_3") (pintype "passive"))
    )
    (net (code "37") (name "unconnected-(J2-Pad4)") (class "Default")
      (node (ref "J2") (pin "4") (pinfunction "4_4") (pintype "passive"))
    )
    (net (code "38") (name "unconnected-(U3-NC-Pad4)") (class "Default")
      (node (ref "U3") (pin "4") (pinfunction "NC_4") (pintype "passive+no_connect"))
    )
    (net (code "39") (name "unconnected-(U3-NC-Pad9)") (class "Default")
      (node (ref "U3") (pin "9") (pinfunction "NC_9") (pintype "passive+no_connect"))
    )
    (net (code "40") (name "unconnected-(U3-NC-Pad11)") (class "Default")
      (node (ref "U3") (pin "11") (pinfunction "NC_11") (pintype "passive+no_connect"))
    )
  )
)
